# QUTMS-TSAL-LEDs.net
KiCad netlist of a schematic drawn in Altium Designer
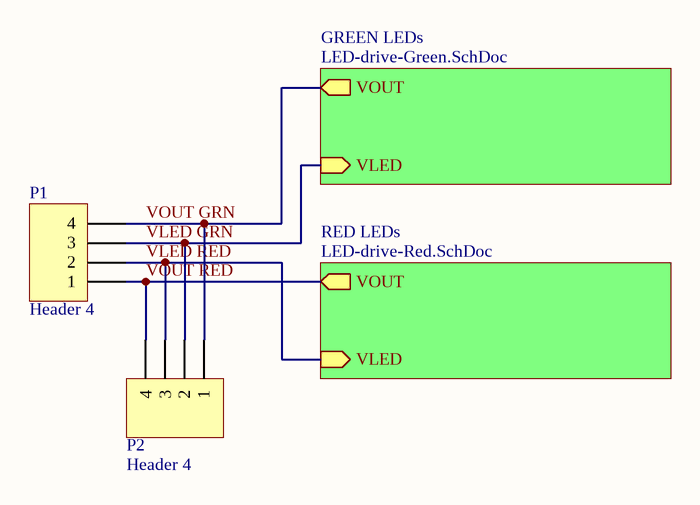
[diagram p0: QUTMS-TSAL-LEDs.SchDoc]

(export (version "E")
  (design (tool "Eeschema 10.0.6"))
  (components
    (comp (ref "P1")
      (value "Header 4")
      (footprint "HDR1X4")
      (description "Header, 4-Pin")
      (fields (field (name "PUBLISHER") "Altium Limited"))
      (libsource (lib "Miscellaneous Connectors") (part "Header 4"))
    )
    (comp (ref "P2")
      (value "Header 4")
      (footprint "HDR1X4")
      (description "Header, 4-Pin")
      (fields (field (name "PUBLISHER") "Altium Limited"))
      (libsource (lib "") (part "Header 4_1"))
    )
  )
  (nets
    (net (code "1") (name "/VLED GRN") (class "Default")
      (node (ref "P1") (pin "3") (pinfunction "3_3") (pintype "passive"))
      (node (ref "P2") (pin "2") (pinfunction "2_2") (pintype "passive"))
    )
    (net (code "2") (name "/VLED RED") (class "Default")
      (node (ref "P1") (pin "2") (pinfunction "2_2") (pintype "passive"))
      (node (ref "P2") (pin "3") (pinfunction "3_3") (pintype "passive"))
    )
    (net (code "3") (name "/VOUT GRN") (class "Default")
      (node (ref "P1") (pin "4") (pinfunction "4_4") (pintype "passive"))
      (node (ref "P2") (pin "1") (pinfunction "1_1") (pintype "passive"))
    )
    (net (code "4") (name "/VOUT RED") (class "Default")
      (node (ref "P1") (pin "1") (pinfunction "1_1") (pintype "passive"))
      (node (ref "P2") (pin "4") (pinfunction "4_4") (pintype "passive"))
    )
  )
)
